# desk-trick-board.net
KiCad netlist of a schematic drawn in EAGLE
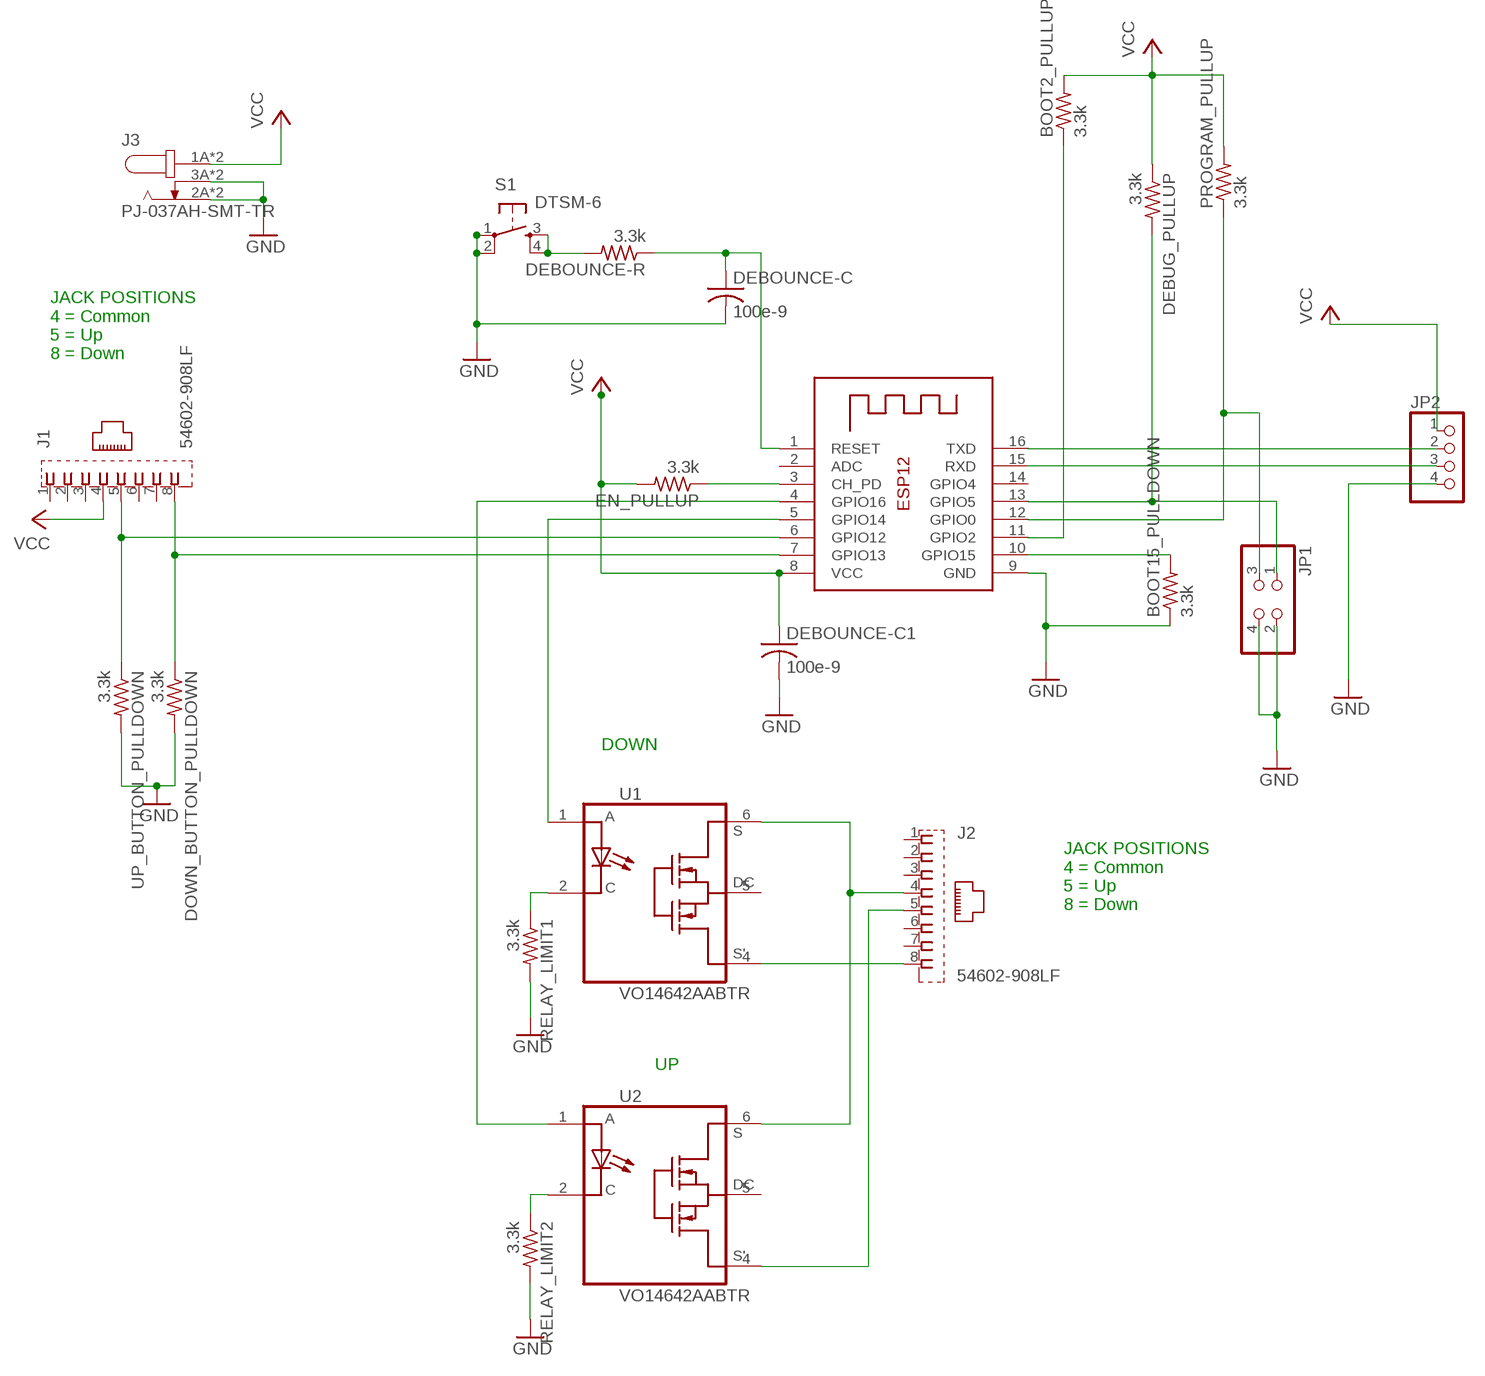
[diagram p0: schematic, sheet 1]

(export (version "E")
  (design (tool "Eeschema 10.0.6"))
  (components
    (comp (ref "BOOT2_PULLUP")
      (value "3.3k")
      (footprint "eagle-import:R0603")
      (libsource (lib "eagle-import") (part "R-US_R0603"))
    )
    (comp (ref "BOOT15_PULLDOWN")
      (value "3.3k")
      (footprint "eagle-import:R0603")
      (libsource (lib "eagle-import") (part "R-US_R0603"))
    )
    (comp (ref "DEBOUNCE-C")
      (value "100e-9")
      (footprint "eagle-import:C0603")
      (libsource (lib "eagle-import") (part "C-USC0603"))
    )
    (comp (ref "DEBOUNCE-C1")
      (value "100e-9")
      (footprint "eagle-import:C0603")
      (libsource (lib "eagle-import") (part "C-USC0603"))
    )
    (comp (ref "DEBOUNCE-R")
      (value "3.3k")
      (footprint "eagle-import:R0603")
      (libsource (lib "eagle-import") (part "R-US_R0603"))
    )
    (comp (ref "DEBUG_PULLUP")
      (value "3.3k")
      (footprint "eagle-import:R0603")
      (libsource (lib "eagle-import") (part "R-US_R0603"))
    )
    (comp (ref "DOWN_BUTTON_PULLDOWN")
      (value "3.3k")
      (footprint "eagle-import:R0603")
      (libsource (lib "eagle-import") (part "R-US_R0603"))
    )
    (comp (ref "EN_PULLUP")
      (value "3.3k")
      (footprint "eagle-import:R0603")
      (libsource (lib "eagle-import") (part "R-US_R0603"))
    )
    (comp (ref "J1")
      (value "54602-908LF")
      (footprint "eagle-import:AMPHENOL_54602-908LF")
      (fields (field (name "DIGI-KEY_PART_NUMBER") "609-1046-ND") (field (name "MF") "Amphenol ICC"))
      (libsource (lib "eagle-import") (part "54602-908LF"))
    )
    (comp (ref "J2")
      (value "54602-908LF")
      (footprint "eagle-import:AMPHENOL_54602-908LF")
      (fields (field (name "DIGI-KEY_PART_NUMBER") "609-1046-ND") (field (name "MF") "Amphenol ICC"))
      (libsource (lib "eagle-import") (part "54602-908LF"))
    )
    (comp (ref "J3")
      (value "PJ-037AH-SMT-TR")
      (footprint "eagle-import:CUI_PJ-037AH-SMT-TR")
      (fields (field (name "MF") "CUI Devices"))
      (libsource (lib "eagle-import") (part "PJ-037AH-SMT-TR"))
    )
    (comp (ref "JP1")
      (value "PINHD-2X2")
      (footprint "eagle-import:2X02")
      (libsource (lib "eagle-import") (part "PINHD-2X2"))
    )
    (comp (ref "JP2")
      (value "PINHD-1X4")
      (footprint "eagle-import:1X04")
      (libsource (lib "eagle-import") (part "PINHD-1X4"))
    )
    (comp (ref "PROGRAM_PULLUP")
      (value "3.3k")
      (footprint "eagle-import:R0603")
      (libsource (lib "eagle-import") (part "R-US_R0603"))
    )
    (comp (ref "RELAY_LIMIT1")
      (value "3.3k")
      (footprint "eagle-import:R0603")
      (libsource (lib "eagle-import") (part "R-US_R0603"))
    )
    (comp (ref "RELAY_LIMIT2")
      (value "3.3k")
      (footprint "eagle-import:R0603")
      (libsource (lib "eagle-import") (part "R-US_R0603"))
    )
    (comp (ref "S1")
      (value "DTSM-6")
      (footprint "eagle-import:DTSM-6")
      (libsource (lib "eagle-import") (part "DTSM-6"))
    )
    (comp (ref "U1")
      (value "VO14642AABTR")
      (footprint "eagle-import:SOIC254P1005X390-6N")
      (fields (field (name "DIGI-KEY_PART_NUMBER") "VO14642AABCT-ND") (field (name "MF") "Vishay"))
      (libsource (lib "eagle-import") (part "VO14642AABTR"))
    )
    (comp (ref "U2")
      (value "VO14642AABTR")
      (footprint "eagle-import:SOIC254P1005X390-6N")
      (fields (field (name "DIGI-KEY_PART_NUMBER") "VO14642AABCT-ND") (field (name "MF") "Vishay"))
      (libsource (lib "eagle-import") (part "VO14642AABTR"))
    )
    (comp (ref "UP_BUTTON_PULLDOWN")
      (value "3.3k")
      (footprint "eagle-import:R0603")
      (libsource (lib "eagle-import") (part "R-US_R0603"))
    )
    (comp (ref "X1")
      (value "ESP-12")
      (footprint "eagle-import:ESP-12")
      (libsource (lib "eagle-import") (part "ESP-12"))
    )
  )
  (nets
    (net (code "1") (name "GND") (class "Default")
      (node (ref "BOOT15_PULLDOWN") (pin "1") (pinfunction "1_1") (pintype "passive"))
      (node (ref "DEBOUNCE-C") (pin "2") (pinfunction "2_2") (pintype "passive"))
      (node (ref "DEBOUNCE-C1") (pin "2") (pinfunction "2_2") (pintype "passive"))
      (node (ref "DOWN_BUTTON_PULLDOWN") (pin "2") (pinfunction "2_2") (pintype "passive"))
      (node (ref "J3") (pin "2A") (pinfunction "2_2A") (pintype "passive"))
      (node (ref "J3") (pin "2B") (pinfunction "2_2B") (pintype "passive"))
      (node (ref "J3") (pin "3A") (pinfunction "3_3A") (pintype "passive"))
      (node (ref "J3") (pin "3B") (pinfunction "3_3B") (pintype "passive"))
      (node (ref "JP1") (pin "2") (pinfunction "2_2") (pintype "passive"))
      (node (ref "JP1") (pin "4") (pinfunction "4_4") (pintype "passive"))
      (node (ref "JP2") (pin "4") (pinfunction "4_4") (pintype "passive"))
      (node (ref "RELAY_LIMIT1") (pin "2") (pinfunction "2_2") (pintype "passive"))
      (node (ref "RELAY_LIMIT2") (pin "2") (pinfunction "2_2") (pintype "passive"))
      (node (ref "S1") (pin "1") (pinfunction "1_1") (pintype "passive"))
      (node (ref "S1") (pin "2") (pinfunction "2_2") (pintype "passive"))
      (node (ref "UP_BUTTON_PULLDOWN") (pin "2") (pinfunction "2_2") (pintype "passive"))
      (node (ref "X1") (pin "9") (pinfunction "GND_9") (pintype "power_in"))
    )
    (net (code "2") (name "Net-(DEBOUNCE-R-Pad2)") (class "Default")
      (node (ref "DEBOUNCE-R") (pin "2") (pinfunction "2_2") (pintype "passive"))
      (node (ref "S1") (pin "3") (pinfunction "3_3") (pintype "passive"))
      (node (ref "S1") (pin "4") (pinfunction "4_4") (pintype "passive"))
    )
    (net (code "3") (name "Net-(U1-A)") (class "Default")
      (node (ref "U1") (pin "1") (pinfunction "A_1") (pintype "passive"))
      (node (ref "X1") (pin "5") (pinfunction "GPIO14_5") (pintype "bidirectional"))
    )
    (net (code "4") (name "Net-(U1-C)") (class "Default")
      (node (ref "RELAY_LIMIT1") (pin "1") (pinfunction "1_1") (pintype "passive"))
      (node (ref "U1") (pin "2") (pinfunction "C_2") (pintype "passive"))
    )
    (net (code "5") (name "Net-(U1-S')") (class "Default")
      (node (ref "J2") (pin "8") (pinfunction "8_8") (pintype "passive"))
      (node (ref "U1") (pin "4") (pinfunction "S'_4") (pintype "passive"))
    )
    (net (code "6") (name "Net-(U1-S)") (class "Default")
      (node (ref "J2") (pin "4") (pinfunction "4_4") (pintype "passive"))
      (node (ref "U1") (pin "6") (pinfunction "S_6") (pintype "passive"))
      (node (ref "U2") (pin "6") (pinfunction "S_6") (pintype "passive"))
    )
    (net (code "7") (name "Net-(U2-A)") (class "Default")
      (node (ref "U2") (pin "1") (pinfunction "A_1") (pintype "passive"))
      (node (ref "X1") (pin "4") (pinfunction "GPIO16_4") (pintype "bidirectional"))
    )
    (net (code "8") (name "Net-(U2-C)") (class "Default")
      (node (ref "RELAY_LIMIT2") (pin "1") (pinfunction "1_1") (pintype "passive"))
      (node (ref "U2") (pin "2") (pinfunction "C_2") (pintype "passive"))
    )
    (net (code "9") (name "Net-(U2-S')") (class "Default")
      (node (ref "J2") (pin "5") (pinfunction "5_5") (pintype "passive"))
      (node (ref "U2") (pin "4") (pinfunction "S'_4") (pintype "passive"))
    )
    (net (code "10") (name "Net-(X1-CH_PD)") (class "Default")
      (node (ref "EN_PULLUP") (pin "1") (pinfunction "1_1") (pintype "passive"))
      (node (ref "X1") (pin "3") (pinfunction "CH_PD_3") (pintype "input"))
    )
    (net (code "11") (name "Net-(X1-GPIO0)") (class "Default")
      (node (ref "JP1") (pin "3") (pinfunction "3_3") (pintype "passive"))
      (node (ref "PROGRAM_PULLUP") (pin "1") (pinfunction "1_1") (pintype "passive"))
      (node (ref "X1") (pin "12") (pinfunction "GPIO0_12") (pintype "bidirectional"))
    )
    (net (code "12") (name "Net-(X1-GPIO2)") (class "Default")
      (node (ref "BOOT2_PULLUP") (pin "1") (pinfunction "1_1") (pintype "passive"))
      (node (ref "X1") (pin "11") (pinfunction "GPIO2_11") (pintype "bidirectional"))
    )
    (net (code "13") (name "Net-(X1-GPIO5)") (class "Default")
      (node (ref "DEBUG_PULLUP") (pin "2") (pinfunction "2_2") (pintype "passive"))
      (node (ref "JP1") (pin "1") (pinfunction "1_1") (pintype "passive"))
      (node (ref "X1") (pin "13") (pinfunction "GPIO5_13") (pintype "bidirectional"))
    )
    (net (code "14") (name "Net-(X1-GPIO12)") (class "Default")
      (node (ref "J1") (pin "5") (pinfunction "5_5") (pintype "passive"))
      (node (ref "UP_BUTTON_PULLDOWN") (pin "1") (pinfunction "1_1") (pintype "passive"))
      (node (ref "X1") (pin "6") (pinfunction "GPIO12_6") (pintype "bidirectional"))
    )
    (net (code "15") (name "Net-(X1-GPIO13)") (class "Default")
      (node (ref "DOWN_BUTTON_PULLDOWN") (pin "1") (pinfunction "1_1") (pintype "passive"))
      (node (ref "J1") (pin "8") (pinfunction "8_8") (pintype "passive"))
      (node (ref "X1") (pin "7") (pinfunction "GPIO13_7") (pintype "bidirectional"))
    )
    (net (code "16") (name "Net-(X1-GPIO15)") (class "Default")
      (node (ref "BOOT15_PULLDOWN") (pin "2") (pinfunction "2_2") (pintype "passive"))
      (node (ref "X1") (pin "10") (pinfunction "GPIO15_10") (pintype "bidirectional"))
    )
    (net (code "17") (name "Net-(X1-RESET)") (class "Default")
      (node (ref "DEBOUNCE-C") (pin "1") (pinfunction "1_1") (pintype "passive"))
      (node (ref "DEBOUNCE-R") (pin "1") (pinfunction "1_1") (pintype "passive"))
      (node (ref "X1") (pin "1") (pinfunction "RESET_1") (pintype "input"))
    )
    (net (code "18") (name "Net-(X1-RXD)") (class "Default")
      (node (ref "JP2") (pin "3") (pinfunction "3_3") (pintype "passive"))
      (node (ref "X1") (pin "15") (pinfunction "RXD_15") (pintype "input"))
    )
    (net (code "19") (name "Net-(X1-TXD)") (class "Default")
      (node (ref "JP2") (pin "2") (pinfunction "2_2") (pintype "passive"))
      (node (ref "X1") (pin "16") (pinfunction "TXD_16") (pintype "output"))
    )
    (net (code "20") (name "VCC") (class "Default")
      (node (ref "BOOT2_PULLUP") (pin "2") (pinfunction "2_2") (pintype "passive"))
      (node (ref "DEBOUNCE-C1") (pin "1") (pinfunction "1_1") (pintype "passive"))
      (node (ref "DEBUG_PULLUP") (pin "1") (pinfunction "1_1") (pintype "passive"))
      (node (ref "EN_PULLUP") (pin "2") (pinfunction "2_2") (pintype "passive"))
      (node (ref "J1") (pin "4") (pinfunction "4_4") (pintype "passive"))
      (node (ref "J3") (pin "1A") (pinfunction "1_1A") (pintype "passive"))
      (node (ref "J3") (pin "1B") (pinfunction "1_1B") (pintype "passive"))
      (node (ref "JP2") (pin "1") (pinfunction "1_1") (pintype "passive"))
      (node (ref "PROGRAM_PULLUP") (pin "2") (pinfunction "2_2") (pintype "passive"))
      (node (ref "X1") (pin "8") (pinfunction "VCC_8") (pintype "power_in"))
    )
    (net (code "21") (name "unconnected-(J1-Pad1)") (class "Default")
      (node (ref "J1") (pin "1") (pinfunction "1_1") (pintype "passive"))
    )
    (net (code "22") (name "unconnected-(J1-Pad2)") (class "Default")
      (node (ref "J1") (pin "2") (pinfunction "2_2") (pintype "passive"))
    )
    (net (code "23") (name "unconnected-(J1-Pad3)") (class "Default")
      (node (ref "J1") (pin "3") (pinfunction "3_3") (pintype "passive"))
    )
    (net (code "24") (name "unconnected-(J1-Pad6)") (class "Default")
      (node (ref "J1") (pin "6") (pinfunction "6_6") (pintype "passive"))
    )
    (net (code "25") (name "unconnected-(J1-Pad7)") (class "Default")
      (node (ref "J1") (pin "7") (pinfunction "7_7") (pintype "passive"))
    )
    (net (code "26") (name "unconnected-(J2-Pad1)") (class "Default")
      (node (ref "J2") (pin "1") (pinfunction "1_1") (pintype "passive"))
    )
    (net (code "27") (name "unconnected-(J2-Pad2)") (class "Default")
      (node (ref "J2") (pin "2") (pinfunction "2_2") (pintype "passive"))
    )
    (net (code "28") (name "unconnected-(J2-Pad3)") (class "Default")
      (node (ref "J2") (pin "3") (pinfunction "3_3") (pintype "passive"))
    )
    (net (code "29") (name "unconnected-(J2-Pad6)") (class "Default")
      (node (ref "J2") (pin "6") (pinfunction "6_6") (pintype "passive"))
    )
    (net (code "30") (name "unconnected-(J2-Pad7)") (class "Default")
      (node (ref "J2") (pin "7") (pinfunction "7_7") (pintype "passive"))
    )
    (net (code "31") (name "unconnected-(U1-DC-Pad5)") (class "Default")
      (node (ref "U1") (pin "5") (pinfunction "DC_5") (pintype "passive"))
    )
    (net (code "32") (name "unconnected-(U2-DC-Pad5)") (class "Default")
      (node (ref "U2") (pin "5") (pinfunction "DC_5") (pintype "passive"))
    )
    (net (code "33") (name "unconnected-(X1-ADC-Pad2)") (class "Default")
      (node (ref "X1") (pin "2") (pinfunction "ADC_2") (pintype "passive"))
    )
    (net (code "34") (name "unconnected-(X1-GPIO4-Pad14)") (class "Default")
      (node (ref "X1") (pin "14") (pinfunction "GPIO4_14") (pintype "bidirectional"))
    )
  )
)
